# USB_UART.net
KiCad netlist of a schematic drawn in Altium Designer
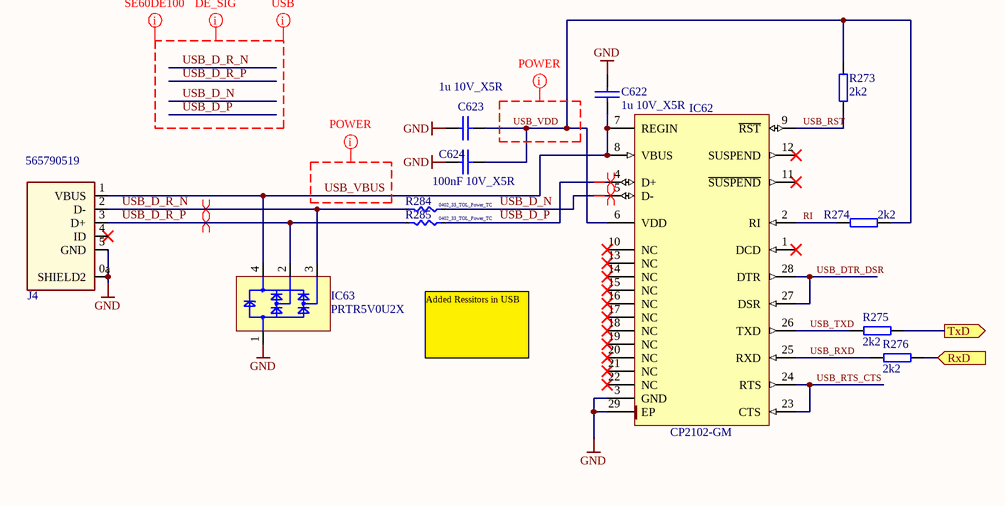
[diagram p0: USB_UART.SchDoc]

(export (version "E")
  (design (tool "Eeschema 10.0.6"))
  (components
    (comp (ref "C622")
      (value "1u 10V_X5R")
      (footprint "0603C")
      (description "Capacitor SMD")
      (libsource (lib "LIBRARY_SCH") (part "CAP_SMD_0603"))
    )
    (comp (ref "C623")
      (value "1u 10V_X5R")
      (footprint "0603C")
      (description "Capacitor SMD")
      (libsource (lib "LIBRARY_SCH") (part "CAP_SMD_0603"))
    )
    (comp (ref "C624")
      (value "100nF 10V_X5R")
      (footprint "0402C")
      (description "Capacitor SMD")
      (libsource (lib "LIBRARY_SCH") (part "CAP_SMD_0402"))
    )
    (comp (ref "IC62")
      (value "CP2102-GM")
      (footprint "QFN50P500X500X100-29N-S335")
      (description "Single-Chip USB to UART Bridge")
      (fields (field (name "MANUFACTURER") "SILICON LABS") (field (name "AUTHOR") "CERN DEM JLC"))
      (libsource (lib "ICs And Semiconductors") (part "CP2102-GM"))
    )
    (comp (ref "IC63")
      (value "PRTR5V0U2X")
      (footprint "sot143b")
      (description "dual 5.5 ESD transient voltage suppressor")
      (libsource (lib "LIBRARY_SCH") (part "D_TVS_PRTR5V0U2X"))
    )
    (comp (ref "J4")
      (value "565790519")
      (footprint "CON_USB_565790519")
      (description "USB mini B connector (Molex)")
      (fields (field (name "PART NUMBER") "10133"))
      (libsource (lib "LIBRARY_SCH") (part "CON_USB_B_MINI_TH"))
    )
    (comp (ref "R273")
      (value "2k2")
      (footprint "0402R")
      (description "SMD Resistor")
      (libsource (lib "LIBRARY_SCH") (part "RES_0402"))
    )
    (comp (ref "R274")
      (value "2k2")
      (footprint "0402R")
      (description "SMD Resistor")
      (libsource (lib "LIBRARY_SCH") (part "RES_0402"))
    )
    (comp (ref "R275")
      (value "2k2")
      (footprint "0402R")
      (description "SMD Resistor")
      (libsource (lib "LIBRARY_SCH") (part "RES_0402"))
    )
    (comp (ref "R276")
      (value "2k2")
      (footprint "0402R")
      (description "SMD Resistor")
      (libsource (lib "LIBRARY_SCH") (part "RES_0402"))
    )
    (comp (ref "R284")
      (value "0402_33_TOL_Power_TC")
      (footprint "RESC1005X40N")
      (fields (field (name "PART NUMBER") "SMT_0402"))
      (libsource (lib "Resistors") (part "Resistor"))
    )
    (comp (ref "R285")
      (value "0402_33_TOL_Power_TC")
      (footprint "RESC1005X40N")
      (fields (field (name "PART NUMBER") "SMT_0402"))
      (libsource (lib "Resistors") (part "Resistor"))
    )
  )
  (nets
    (net (code "1") (name "/RI") (class "Default")
      (node (ref "IC62") (pin "2") (pinfunction "RI_2") (pintype "input"))
      (node (ref "R274") (pin "1") (pinfunction "1_1") (pintype "passive"))
    )
    (net (code "2") (name "/RxD") (class "Default")
      (node (ref "R276") (pin "1") (pinfunction "1_1") (pintype "passive"))
    )
    (net (code "3") (name "/TxD") (class "Default")
      (node (ref "R275") (pin "1") (pinfunction "1_1") (pintype "passive"))
    )
    (net (code "4") (name "/USB_DTR_DSR") (class "Default")
      (node (ref "IC62") (pin "27") (pinfunction "DSR_27") (pintype "input"))
      (node (ref "IC62") (pin "28") (pinfunction "DTR_28") (pintype "output"))
    )
    (net (code "5") (name "/USB_D_N") (class "Default")
      (node (ref "IC62") (pin "5") (pinfunction "D-_5") (pintype "bidirectional"))
      (node (ref "R284") (pin "2") (pinfunction "-_2") (pintype "passive"))
    )
    (net (code "6") (name "/USB_D_P") (class "Default")
      (node (ref "IC62") (pin "4") (pinfunction "D+_4") (pintype "bidirectional"))
      (node (ref "R285") (pin "2") (pinfunction "-_2") (pintype "passive"))
    )
    (net (code "7") (name "/USB_D_R_N") (class "Default")
      (node (ref "IC63") (pin "3") (pinfunction "3_3") (pintype "passive"))
      (node (ref "J4") (pin "2") (pinfunction "D-_2") (pintype "passive"))
      (node (ref "R284") (pin "1") (pinfunction "+_1") (pintype "passive"))
    )
    (net (code "8") (name "/USB_D_R_P") (class "Default")
      (node (ref "IC63") (pin "2") (pinfunction "2_2") (pintype "passive"))
      (node (ref "J4") (pin "3") (pinfunction "D+_3") (pintype "passive"))
      (node (ref "R285") (pin "1") (pinfunction "+_1") (pintype "passive"))
    )
    (net (code "9") (name "/USB_RST") (class "Default")
      (node (ref "IC62") (pin "9") (pinfunction "~{RST}_9") (pintype "bidirectional"))
      (node (ref "R273") (pin "1") (pinfunction "1_1") (pintype "passive"))
    )
    (net (code "10") (name "/USB_RTS_CTS") (class "Default")
      (node (ref "IC62") (pin "23") (pinfunction "CTS_23") (pintype "input"))
      (node (ref "IC62") (pin "24") (pinfunction "RTS_24") (pintype "output"))
    )
    (net (code "11") (name "/USB_RXD") (class "Default")
      (node (ref "IC62") (pin "25") (pinfunction "RXD_25") (pintype "input"))
      (node (ref "R276") (pin "2") (pinfunction "2_2") (pintype "passive"))
    )
    (net (code "12") (name "/USB_TXD") (class "Default")
      (node (ref "IC62") (pin "26") (pinfunction "TXD_26") (pintype "output"))
      (node (ref "R275") (pin "2") (pinfunction "2_2") (pintype "passive"))
    )
    (net (code "13") (name "/USB_VBUS") (class "Default")
      (node (ref "C622") (pin "2") (pinfunction "2_2") (pintype "passive"))
      (node (ref "IC62") (pin "7") (pinfunction "REGIN_7") (pintype "power_in"))
      (node (ref "IC62") (pin "8") (pinfunction "VBUS_8") (pintype "input"))
      (node (ref "IC63") (pin "4") (pinfunction "4_4") (pintype "passive"))
      (node (ref "J4") (pin "1") (pinfunction "VBUS_1") (pintype "passive"))
    )
    (net (code "14") (name "/USB_VDD") (class "Default")
      (node (ref "C623") (pin "2") (pinfunction "2_2") (pintype "passive"))
      (node (ref "C624") (pin "2") (pinfunction "2_2") (pintype "passive"))
      (node (ref "IC62") (pin "6") (pinfunction "VDD_6") (pintype "power_in"))
      (node (ref "R273") (pin "2") (pinfunction "2_2") (pintype "passive"))
      (node (ref "R274") (pin "2") (pinfunction "2_2") (pintype "passive"))
    )
    (net (code "15") (name "GND") (class "Default")
      (node (ref "C622") (pin "1") (pinfunction "1_1") (pintype "passive"))
      (node (ref "C623") (pin "1") (pinfunction "1_1") (pintype "passive"))
      (node (ref "C624") (pin "1") (pinfunction "1_1") (pintype "passive"))
      (node (ref "IC62") (pin "29") (pinfunction "EP_29") (pintype "power_in"))
      (node (ref "IC62") (pin "3") (pinfunction "GND_3") (pintype "power_in"))
      (node (ref "IC63") (pin "1") (pinfunction "1_1") (pintype "passive"))
      (node (ref "J4") (pin "0") (pinfunction "SHIELD2_0") (pintype "passive"))
      (node (ref "J4") (pin "0a") (pinfunction "SHIELD2_0a") (pintype "passive"))
      (node (ref "J4") (pin "5") (pinfunction "GND_5") (pintype "passive"))
    )
    (net (code "16") (name "unconnected-(IC62-DCD-Pad1)") (class "Default")
      (node (ref "IC62") (pin "1") (pinfunction "DCD_1") (pintype "input+no_connect"))
    )
    (net (code "17") (name "unconnected-(IC62-NC-Pad10)") (class "Default")
      (node (ref "IC62") (pin "10") (pinfunction "NC_10") (pintype "passive+no_connect"))
    )
    (net (code "18") (name "unconnected-(IC62-NC-Pad13)") (class "Default")
      (node (ref "IC62") (pin "13") (pinfunction "NC_13") (pintype "passive+no_connect"))
    )
    (net (code "19") (name "unconnected-(IC62-NC-Pad14)") (class "Default")
      (node (ref "IC62") (pin "14") (pinfunction "NC_14") (pintype "passive+no_connect"))
    )
    (net (code "20") (name "unconnected-(IC62-NC-Pad15)") (class "Default")
      (node (ref "IC62") (pin "15") (pinfunction "NC_15") (pintype "passive+no_connect"))
    )
    (net (code "21") (name "unconnected-(IC62-NC-Pad16)") (class "Default")
      (node (ref "IC62") (pin "16") (pinfunction "NC_16") (pintype "passive+no_connect"))
    )
    (net (code "22") (name "unconnected-(IC62-NC-Pad17)") (class "Default")
      (node (ref "IC62") (pin "17") (pinfunction "NC_17") (pintype "passive+no_connect"))
    )
    (net (code "23") (name "unconnected-(IC62-NC-Pad18)") (class "Default")
      (node (ref "IC62") (pin "18") (pinfunction "NC_18") (pintype "passive+no_connect"))
    )
    (net (code "24") (name "unconnected-(IC62-NC-Pad19)") (class "Default")
      (node (ref "IC62") (pin "19") (pinfunction "NC_19") (pintype "passive+no_connect"))
    )
    (net (code "25") (name "unconnected-(IC62-NC-Pad20)") (class "Default")
      (node (ref "IC62") (pin "20") (pinfunction "NC_20") (pintype "passive+no_connect"))
    )
    (net (code "26") (name "unconnected-(IC62-NC-Pad21)") (class "Default")
      (node (ref "IC62") (pin "21") (pinfunction "NC_21") (pintype "passive+no_connect"))
    )
    (net (code "27") (name "unconnected-(IC62-NC-Pad22)") (class "Default")
      (node (ref "IC62") (pin "22") (pinfunction "NC_22") (pintype "passive+no_connect"))
    )
    (net (code "28") (name "unconnected-(IC62-SUSPEND-Pad12)") (class "Default")
      (node (ref "IC62") (pin "12") (pinfunction "SUSPEND_12") (pintype "output+no_connect"))
    )
    (net (code "29") (name "unconnected-(IC62-~{SUSPEND}-Pad11)") (class "Default")
      (node (ref "IC62") (pin "11") (pinfunction "~{SUSPEND}_11") (pintype "output+no_connect"))
    )
    (net (code "30") (name "unconnected-(J4-ID-Pad4)") (class "Default")
      (node (ref "J4") (pin "4") (pinfunction "ID_4") (pintype "passive+no_connect"))
    )
  )
)
